# Nova_32kw_FRAM_piggyback.net
KiCad netlist of a schematic drawn in EasyEDA Pro
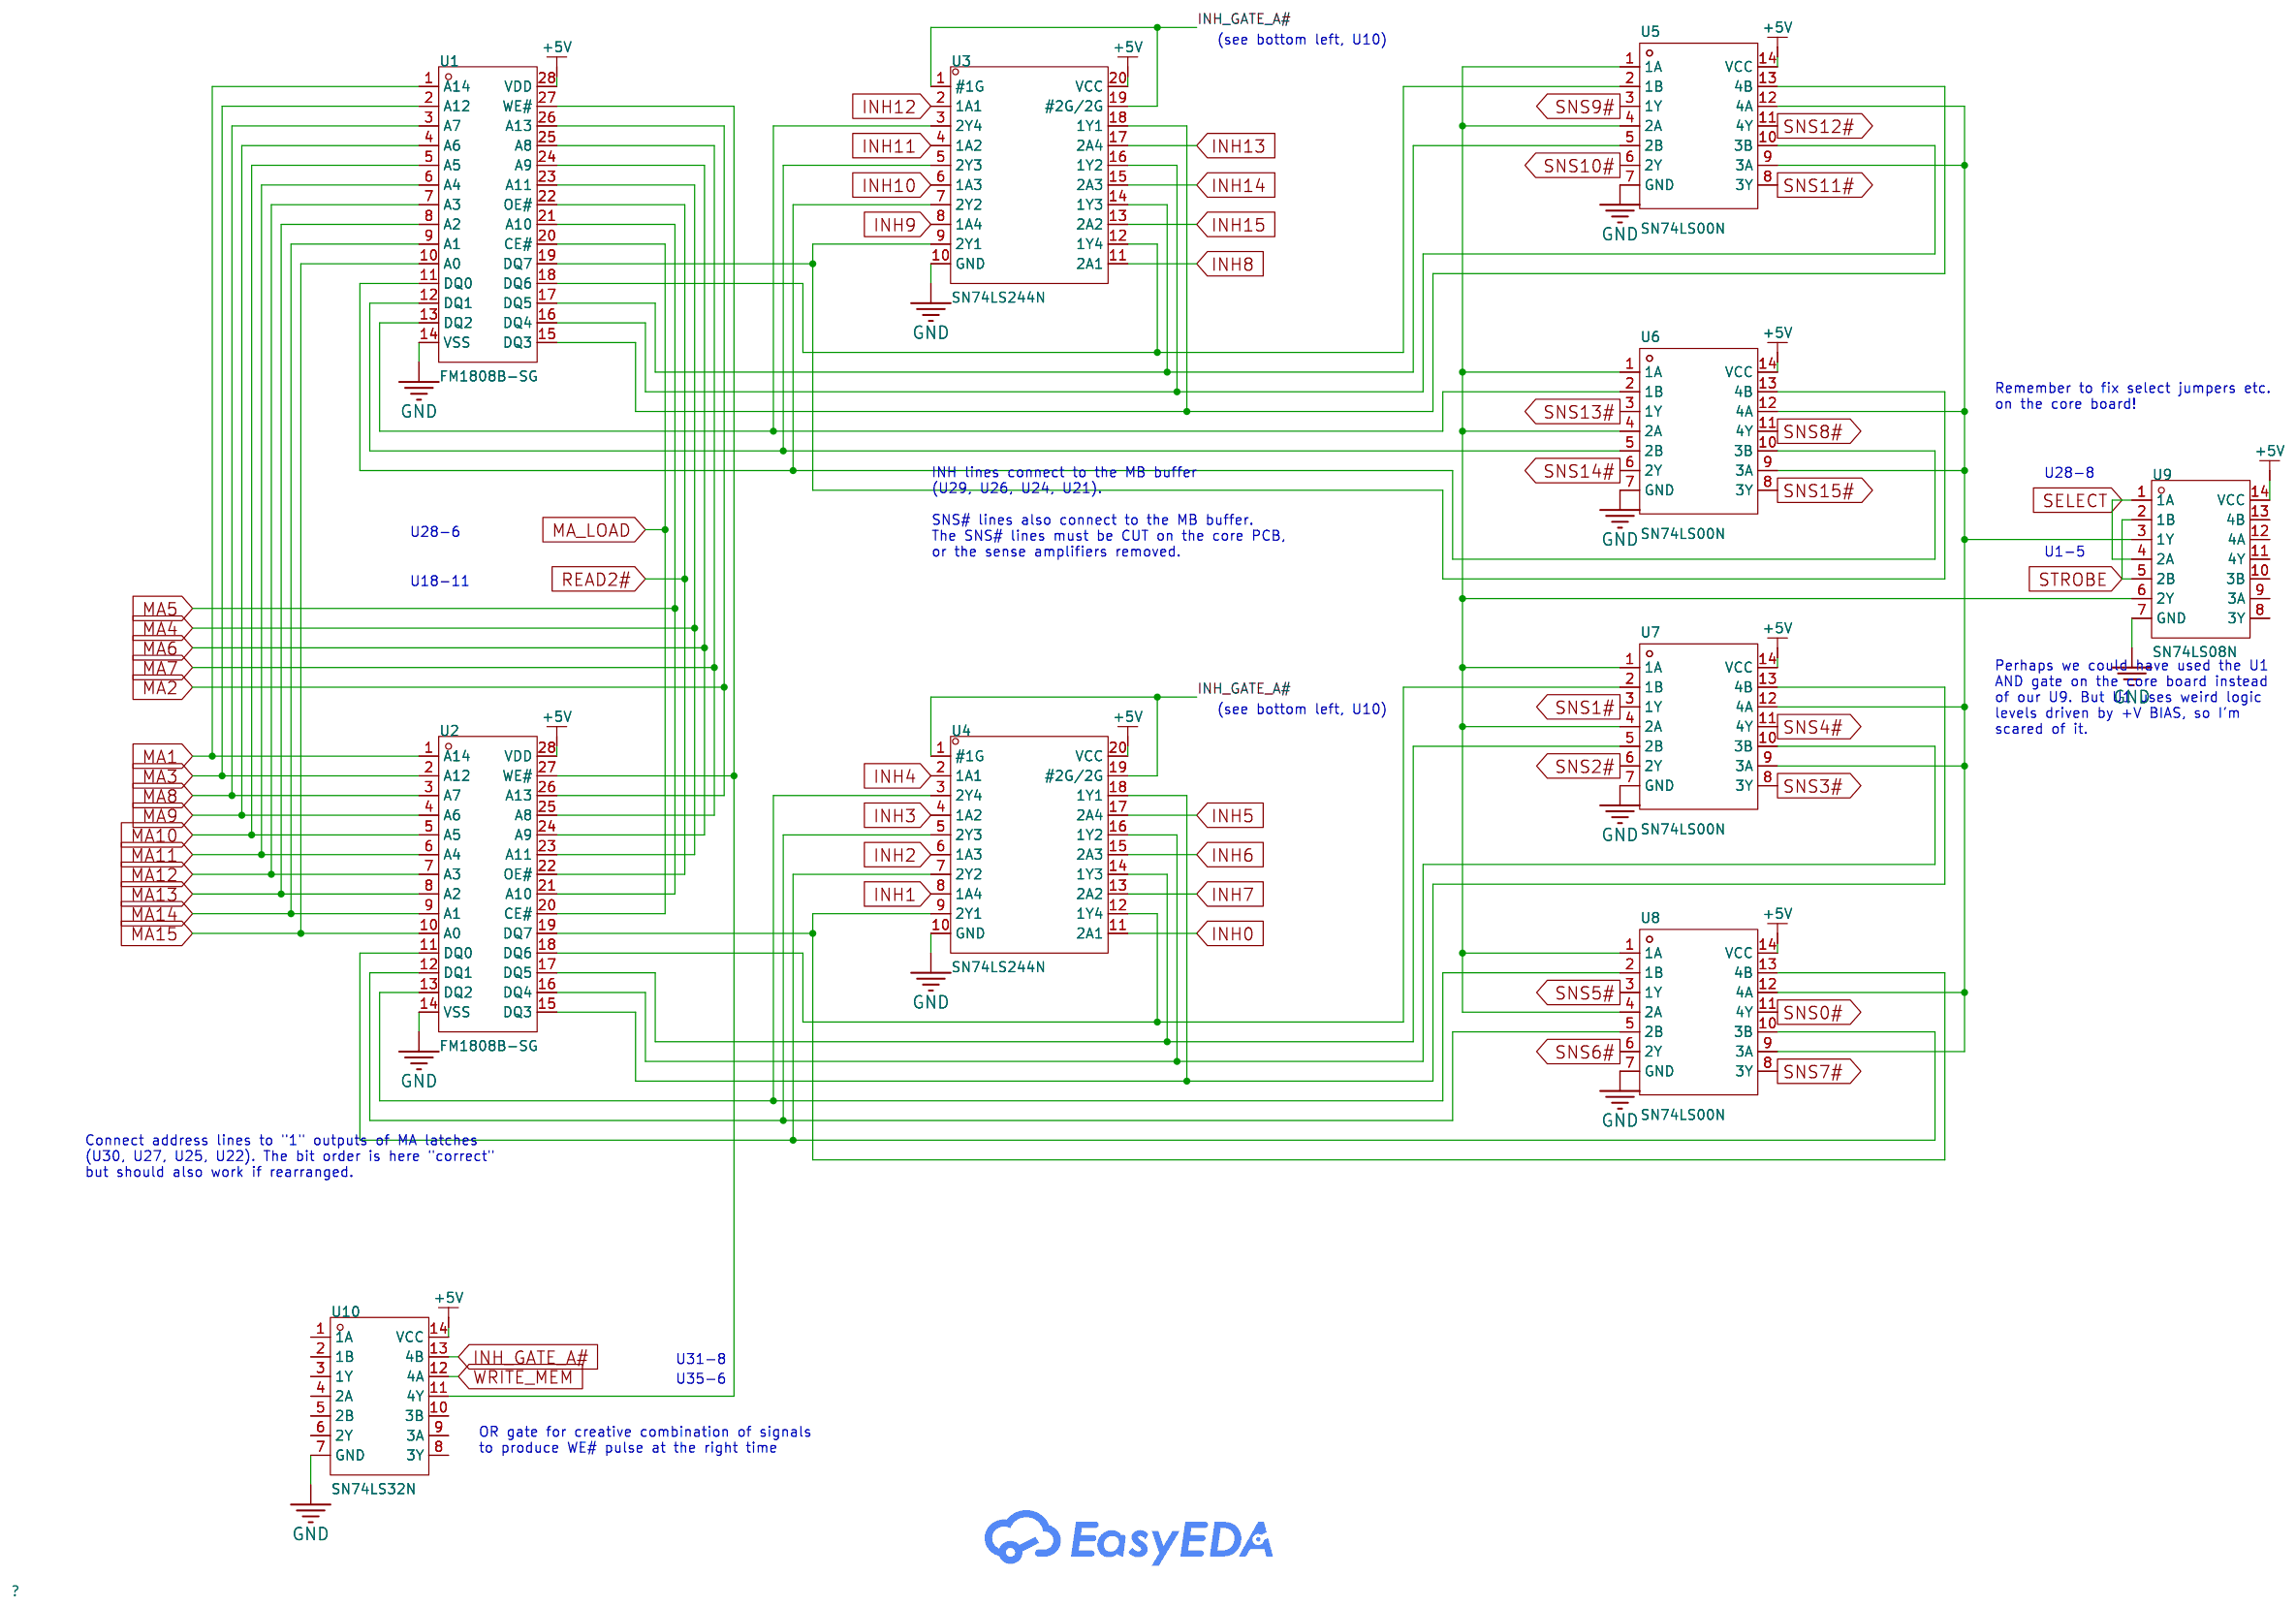
[diagram p0: schematic sheet]

(export (version "E")
  (design (tool "Eeschema 10.0.6"))
  (components
    (comp (ref "U1")
      (value "FM1808B-SG")
      (footprint "easyedapro:SOIC-28_L17.9-W7.5-P1.27-LS10.3-BL")
      (fields (field (name "Manufacturer") "Infineon/CYPRESS(赛普拉斯)"))
      (libsource (lib "easyedapro") (part "FM1808B-SG_C2953762"))
    )
    (comp (ref "U2")
      (value "FM1808B-SG")
      (footprint "easyedapro:SOIC-28_L17.9-W7.5-P1.27-LS10.3-BL")
      (fields (field (name "Manufacturer") "Infineon/CYPRESS(赛普拉斯)"))
      (libsource (lib "easyedapro") (part "FM1808B-SG_C2953762"))
    )
    (comp (ref "U3")
      (value "SN74LS244N")
      (footprint "easyedapro:DIP-20_L25.5-W10.0-P2.54-LS7.6-BL")
      (fields (field (name "Manufacturer") "TI(德州仪器)"))
      (libsource (lib "easyedapro") (part "SN74LS244N"))
    )
    (comp (ref "U4")
      (value "SN74LS244N")
      (footprint "easyedapro:DIP-20_L25.5-W10.0-P2.54-LS7.6-BL")
      (fields (field (name "Manufacturer") "TI(德州仪器)"))
      (libsource (lib "easyedapro") (part "SN74LS244N"))
    )
    (comp (ref "U5")
      (value "SN74LS00N")
      (footprint "easyedapro:PDIP-14_L19.7-W6.6-P2.54-LS8.3-BL")
      (fields (field (name "Manufacturer") "TI(德州仪器)"))
      (libsource (lib "easyedapro") (part "SN74LS00N"))
    )
    (comp (ref "U6")
      (value "SN74LS00N")
      (footprint "easyedapro:PDIP-14_L19.7-W6.6-P2.54-LS8.3-BL")
      (fields (field (name "Manufacturer") "TI(德州仪器)"))
      (libsource (lib "easyedapro") (part "SN74LS00N"))
    )
    (comp (ref "U7")
      (value "SN74LS00N")
      (footprint "easyedapro:PDIP-14_L19.7-W6.6-P2.54-LS8.3-BL")
      (fields (field (name "Manufacturer") "TI(德州仪器)"))
      (libsource (lib "easyedapro") (part "SN74LS00N"))
    )
    (comp (ref "U8")
      (value "SN74LS00N")
      (footprint "easyedapro:PDIP-14_L19.7-W6.6-P2.54-LS8.3-BL")
      (fields (field (name "Manufacturer") "TI(德州仪器)"))
      (libsource (lib "easyedapro") (part "SN74LS00N"))
    )
    (comp (ref "U9")
      (value "SN74LS08N")
      (footprint "easyedapro:PDIP-14_L19.3-W6.4-P2.54-LS7.9-BL-1")
      (fields (field (name "Manufacturer") "TI(德州仪器)"))
      (libsource (lib "easyedapro") (part "SN74LS08N"))
    )
    (comp (ref "U10")
      (value "SN74LS32N")
      (footprint "easyedapro:PDIP-14_L19.6-W6.5-P2.54-LS7.9-BL")
      (fields (field (name "Manufacturer") "TI(德州仪器)"))
      (libsource (lib "easyedapro") (part "SN74LS32N"))
    )
  )
  (nets
    (net (code "1") (name "+5V") (class "Default")
      (node (ref "U1") (pin "28") (pinfunction "VDD_28") (pintype "unspecified"))
      (node (ref "U10") (pin "14") (pinfunction "VCC_14") (pintype "input"))
      (node (ref "U2") (pin "28") (pinfunction "VDD_28") (pintype "unspecified"))
      (node (ref "U3") (pin "20") (pinfunction "VCC_20") (pintype "input"))
      (node (ref "U4") (pin "20") (pinfunction "VCC_20") (pintype "input"))
      (node (ref "U5") (pin "14") (pinfunction "VCC_14") (pintype "unspecified"))
      (node (ref "U6") (pin "14") (pinfunction "VCC_14") (pintype "unspecified"))
      (node (ref "U7") (pin "14") (pinfunction "VCC_14") (pintype "unspecified"))
      (node (ref "U8") (pin "14") (pinfunction "VCC_14") (pintype "unspecified"))
      (node (ref "U9") (pin "14") (pinfunction "VCC_14") (pintype "unspecified"))
    )
    (net (code "2") (name "GND") (class "Default")
      (node (ref "U1") (pin "14") (pinfunction "VSS_14") (pintype "unspecified"))
      (node (ref "U10") (pin "7") (pinfunction "GND_7") (pintype "input"))
      (node (ref "U2") (pin "14") (pinfunction "VSS_14") (pintype "unspecified"))
      (node (ref "U3") (pin "10") (pinfunction "GND_10") (pintype "input"))
      (node (ref "U4") (pin "10") (pinfunction "GND_10") (pintype "input"))
      (node (ref "U5") (pin "7") (pinfunction "GND_7") (pintype "unspecified"))
      (node (ref "U6") (pin "7") (pinfunction "GND_7") (pintype "unspecified"))
      (node (ref "U7") (pin "7") (pinfunction "GND_7") (pintype "unspecified"))
      (node (ref "U8") (pin "7") (pinfunction "GND_7") (pintype "unspecified"))
      (node (ref "U9") (pin "7") (pinfunction "GND_7") (pintype "unspecified"))
    )
    (net (code "3") (name "INH0") (class "Default")
      (node (ref "U4") (pin "11") (pinfunction "2A1_11") (pintype "input"))
    )
    (net (code "4") (name "INH1") (class "Default")
      (node (ref "U4") (pin "8") (pinfunction "1A4_8") (pintype "input"))
    )
    (net (code "5") (name "INH2") (class "Default")
      (node (ref "U4") (pin "6") (pinfunction "1A3_6") (pintype "input"))
    )
    (net (code "6") (name "INH3") (class "Default")
      (node (ref "U4") (pin "4") (pinfunction "1A2_4") (pintype "input"))
    )
    (net (code "7") (name "INH4") (class "Default")
      (node (ref "U4") (pin "2") (pinfunction "1A1_2") (pintype "input"))
    )
    (net (code "8") (name "INH5") (class "Default")
      (node (ref "U4") (pin "17") (pinfunction "2A4_17") (pintype "input"))
    )
    (net (code "9") (name "INH6") (class "Default")
      (node (ref "U4") (pin "15") (pinfunction "2A3_15") (pintype "input"))
    )
    (net (code "10") (name "INH7") (class "Default")
      (node (ref "U4") (pin "13") (pinfunction "2A2_13") (pintype "input"))
    )
    (net (code "11") (name "INH8") (class "Default")
      (node (ref "U3") (pin "11") (pinfunction "2A1_11") (pintype "input"))
    )
    (net (code "12") (name "INH9") (class "Default")
      (node (ref "U3") (pin "8") (pinfunction "1A4_8") (pintype "input"))
    )
    (net (code "13") (name "INH10") (class "Default")
      (node (ref "U3") (pin "6") (pinfunction "1A3_6") (pintype "input"))
    )
    (net (code "14") (name "INH11") (class "Default")
      (node (ref "U3") (pin "4") (pinfunction "1A2_4") (pintype "input"))
    )
    (net (code "15") (name "INH12") (class "Default")
      (node (ref "U3") (pin "2") (pinfunction "1A1_2") (pintype "input"))
    )
    (net (code "16") (name "INH13") (class "Default")
      (node (ref "U3") (pin "17") (pinfunction "2A4_17") (pintype "input"))
    )
    (net (code "17") (name "INH14") (class "Default")
      (node (ref "U3") (pin "15") (pinfunction "2A3_15") (pintype "input"))
    )
    (net (code "18") (name "INH15") (class "Default")
      (node (ref "U3") (pin "13") (pinfunction "2A2_13") (pintype "input"))
    )
    (net (code "19") (name "INH_GATE_A#") (class "Default")
      (node (ref "U10") (pin "13") (pinfunction "4B_13") (pintype "input"))
      (node (ref "U3") (pin "1") (pinfunction "#1G_1") (pintype "input"))
      (node (ref "U3") (pin "19") (pinfunction "#2G/2G_19") (pintype "input"))
      (node (ref "U4") (pin "1") (pinfunction "#1G_1") (pintype "input"))
      (node (ref "U4") (pin "19") (pinfunction "#2G/2G_19") (pintype "input"))
    )
    (net (code "20") (name "MA1") (class "Default")
      (node (ref "U1") (pin "1") (pinfunction "A14_1") (pintype "unspecified"))
      (node (ref "U2") (pin "1") (pinfunction "A14_1") (pintype "unspecified"))
    )
    (net (code "21") (name "MA2") (class "Default")
      (node (ref "U1") (pin "26") (pinfunction "A13_26") (pintype "unspecified"))
      (node (ref "U2") (pin "26") (pinfunction "A13_26") (pintype "unspecified"))
    )
    (net (code "22") (name "MA3") (class "Default")
      (node (ref "U1") (pin "2") (pinfunction "A12_2") (pintype "unspecified"))
      (node (ref "U2") (pin "2") (pinfunction "A12_2") (pintype "unspecified"))
    )
    (net (code "23") (name "MA4") (class "Default")
      (node (ref "U1") (pin "23") (pinfunction "A11_23") (pintype "unspecified"))
      (node (ref "U2") (pin "23") (pinfunction "A11_23") (pintype "unspecified"))
    )
    (net (code "24") (name "MA5") (class "Default")
      (node (ref "U1") (pin "21") (pinfunction "A10_21") (pintype "unspecified"))
      (node (ref "U2") (pin "21") (pinfunction "A10_21") (pintype "unspecified"))
    )
    (net (code "25") (name "MA6") (class "Default")
      (node (ref "U1") (pin "24") (pinfunction "A9_24") (pintype "unspecified"))
      (node (ref "U2") (pin "24") (pinfunction "A9_24") (pintype "unspecified"))
    )
    (net (code "26") (name "MA7") (class "Default")
      (node (ref "U1") (pin "25") (pinfunction "A8_25") (pintype "unspecified"))
      (node (ref "U2") (pin "25") (pinfunction "A8_25") (pintype "unspecified"))
    )
    (net (code "27") (name "MA8") (class "Default")
      (node (ref "U1") (pin "3") (pinfunction "A7_3") (pintype "unspecified"))
      (node (ref "U2") (pin "3") (pinfunction "A7_3") (pintype "unspecified"))
    )
    (net (code "28") (name "MA9") (class "Default")
      (node (ref "U1") (pin "4") (pinfunction "A6_4") (pintype "unspecified"))
      (node (ref "U2") (pin "4") (pinfunction "A6_4") (pintype "unspecified"))
    )
    (net (code "29") (name "MA10") (class "Default")
      (node (ref "U1") (pin "5") (pinfunction "A5_5") (pintype "unspecified"))
      (node (ref "U2") (pin "5") (pinfunction "A5_5") (pintype "unspecified"))
    )
    (net (code "30") (name "MA11") (class "Default")
      (node (ref "U1") (pin "6") (pinfunction "A4_6") (pintype "unspecified"))
      (node (ref "U2") (pin "6") (pinfunction "A4_6") (pintype "unspecified"))
    )
    (net (code "31") (name "MA12") (class "Default")
      (node (ref "U1") (pin "7") (pinfunction "A3_7") (pintype "unspecified"))
      (node (ref "U2") (pin "7") (pinfunction "A3_7") (pintype "unspecified"))
    )
    (net (code "32") (name "MA13") (class "Default")
      (node (ref "U1") (pin "8") (pinfunction "A2_8") (pintype "unspecified"))
      (node (ref "U2") (pin "8") (pinfunction "A2_8") (pintype "unspecified"))
    )
    (net (code "33") (name "MA14") (class "Default")
      (node (ref "U1") (pin "9") (pinfunction "A1_9") (pintype "unspecified"))
      (node (ref "U2") (pin "9") (pinfunction "A1_9") (pintype "unspecified"))
    )
    (net (code "34") (name "MA15") (class "Default")
      (node (ref "U1") (pin "10") (pinfunction "A0_10") (pintype "unspecified"))
      (node (ref "U2") (pin "10") (pinfunction "A0_10") (pintype "unspecified"))
    )
    (net (code "35") (name "MA_LOAD") (class "Default")
      (node (ref "U1") (pin "20") (pinfunction "CE#_20") (pintype "unspecified"))
      (node (ref "U2") (pin "20") (pinfunction "CE#_20") (pintype "unspecified"))
    )
    (net (code "36") (name "Net-(U1-DQ0)") (class "Default")
      (node (ref "U1") (pin "11") (pinfunction "DQ0_11") (pintype "unspecified"))
      (node (ref "U3") (pin "7") (pinfunction "2Y2_7") (pintype "input"))
      (node (ref "U6") (pin "10") (pinfunction "3B_10") (pintype "unspecified"))
    )
    (net (code "37") (name "Net-(U1-DQ1)") (class "Default")
      (node (ref "U1") (pin "12") (pinfunction "DQ1_12") (pintype "unspecified"))
      (node (ref "U3") (pin "5") (pinfunction "2Y3_5") (pintype "input"))
      (node (ref "U6") (pin "5") (pinfunction "2B_5") (pintype "unspecified"))
    )
    (net (code "38") (name "Net-(U1-DQ2)") (class "Default")
      (node (ref "U1") (pin "13") (pinfunction "DQ2_13") (pintype "unspecified"))
      (node (ref "U3") (pin "3") (pinfunction "2Y4_3") (pintype "input"))
      (node (ref "U6") (pin "2") (pinfunction "1B_2") (pintype "unspecified"))
    )
    (net (code "39") (name "Net-(U1-DQ3)") (class "Default")
      (node (ref "U1") (pin "15") (pinfunction "DQ3_15") (pintype "unspecified"))
      (node (ref "U3") (pin "18") (pinfunction "1Y1_18") (pintype "input"))
      (node (ref "U5") (pin "13") (pinfunction "4B_13") (pintype "unspecified"))
    )
    (net (code "40") (name "Net-(U1-DQ4)") (class "Default")
      (node (ref "U1") (pin "16") (pinfunction "DQ4_16") (pintype "unspecified"))
      (node (ref "U3") (pin "16") (pinfunction "1Y2_16") (pintype "input"))
      (node (ref "U5") (pin "10") (pinfunction "3B_10") (pintype "unspecified"))
    )
    (net (code "41") (name "Net-(U1-DQ5)") (class "Default")
      (node (ref "U1") (pin "17") (pinfunction "DQ5_17") (pintype "unspecified"))
      (node (ref "U3") (pin "14") (pinfunction "1Y3_14") (pintype "input"))
      (node (ref "U5") (pin "5") (pinfunction "2B_5") (pintype "unspecified"))
    )
    (net (code "42") (name "Net-(U1-DQ6)") (class "Default")
      (node (ref "U1") (pin "18") (pinfunction "DQ6_18") (pintype "unspecified"))
      (node (ref "U3") (pin "12") (pinfunction "1Y4_12") (pintype "input"))
      (node (ref "U5") (pin "2") (pinfunction "1B_2") (pintype "unspecified"))
    )
    (net (code "43") (name "Net-(U1-DQ7)") (class "Default")
      (node (ref "U1") (pin "19") (pinfunction "DQ7_19") (pintype "unspecified"))
      (node (ref "U3") (pin "9") (pinfunction "2Y1_9") (pintype "input"))
      (node (ref "U6") (pin "13") (pinfunction "4B_13") (pintype "unspecified"))
    )
    (net (code "44") (name "Net-(U1-WE#)") (class "Default")
      (node (ref "U1") (pin "27") (pinfunction "WE#_27") (pintype "unspecified"))
      (node (ref "U10") (pin "11") (pinfunction "4Y_11") (pintype "input"))
      (node (ref "U2") (pin "27") (pinfunction "WE#_27") (pintype "unspecified"))
    )
    (net (code "45") (name "Net-(U2-DQ0)") (class "Default")
      (node (ref "U2") (pin "11") (pinfunction "DQ0_11") (pintype "unspecified"))
      (node (ref "U4") (pin "7") (pinfunction "2Y2_7") (pintype "input"))
      (node (ref "U8") (pin "10") (pinfunction "3B_10") (pintype "unspecified"))
    )
    (net (code "46") (name "Net-(U2-DQ1)") (class "Default")
      (node (ref "U2") (pin "12") (pinfunction "DQ1_12") (pintype "unspecified"))
      (node (ref "U4") (pin "5") (pinfunction "2Y3_5") (pintype "input"))
      (node (ref "U8") (pin "5") (pinfunction "2B_5") (pintype "unspecified"))
    )
    (net (code "47") (name "Net-(U2-DQ2)") (class "Default")
      (node (ref "U2") (pin "13") (pinfunction "DQ2_13") (pintype "unspecified"))
      (node (ref "U4") (pin "3") (pinfunction "2Y4_3") (pintype "input"))
      (node (ref "U8") (pin "2") (pinfunction "1B_2") (pintype "unspecified"))
    )
    (net (code "48") (name "Net-(U2-DQ3)") (class "Default")
      (node (ref "U2") (pin "15") (pinfunction "DQ3_15") (pintype "unspecified"))
      (node (ref "U4") (pin "18") (pinfunction "1Y1_18") (pintype "input"))
      (node (ref "U7") (pin "13") (pinfunction "4B_13") (pintype "unspecified"))
    )
    (net (code "49") (name "Net-(U2-DQ4)") (class "Default")
      (node (ref "U2") (pin "16") (pinfunction "DQ4_16") (pintype "unspecified"))
      (node (ref "U4") (pin "16") (pinfunction "1Y2_16") (pintype "input"))
      (node (ref "U7") (pin "10") (pinfunction "3B_10") (pintype "unspecified"))
    )
    (net (code "50") (name "Net-(U2-DQ5)") (class "Default")
      (node (ref "U2") (pin "17") (pinfunction "DQ5_17") (pintype "unspecified"))
      (node (ref "U4") (pin "14") (pinfunction "1Y3_14") (pintype "input"))
      (node (ref "U7") (pin "5") (pinfunction "2B_5") (pintype "unspecified"))
    )
    (net (code "51") (name "Net-(U2-DQ6)") (class "Default")
      (node (ref "U2") (pin "18") (pinfunction "DQ6_18") (pintype "unspecified"))
      (node (ref "U4") (pin "12") (pinfunction "1Y4_12") (pintype "input"))
      (node (ref "U7") (pin "2") (pinfunction "1B_2") (pintype "unspecified"))
    )
    (net (code "52") (name "Net-(U2-DQ7)") (class "Default")
      (node (ref "U2") (pin "19") (pinfunction "DQ7_19") (pintype "unspecified"))
      (node (ref "U4") (pin "9") (pinfunction "2Y1_9") (pintype "input"))
      (node (ref "U8") (pin "13") (pinfunction "4B_13") (pintype "unspecified"))
    )
    (net (code "53") (name "Net-(U5-1A)") (class "Default")
      (node (ref "U5") (pin "1") (pinfunction "1A_1") (pintype "unspecified"))
      (node (ref "U5") (pin "4") (pinfunction "2A_4") (pintype "unspecified"))
      (node (ref "U6") (pin "1") (pinfunction "1A_1") (pintype "unspecified"))
      (node (ref "U6") (pin "4") (pinfunction "2A_4") (pintype "unspecified"))
      (node (ref "U7") (pin "1") (pinfunction "1A_1") (pintype "unspecified"))
      (node (ref "U7") (pin "4") (pinfunction "2A_4") (pintype "unspecified"))
      (node (ref "U8") (pin "1") (pinfunction "1A_1") (pintype "unspecified"))
      (node (ref "U8") (pin "4") (pinfunction "2A_4") (pintype "unspecified"))
      (node (ref "U9") (pin "6") (pinfunction "2Y_6") (pintype "unspecified"))
    )
    (net (code "54") (name "Net-(U5-3A)") (class "Default")
      (node (ref "U5") (pin "12") (pinfunction "4A_12") (pintype "unspecified"))
      (node (ref "U5") (pin "9") (pinfunction "3A_9") (pintype "unspecified"))
      (node (ref "U6") (pin "12") (pinfunction "4A_12") (pintype "unspecified"))
      (node (ref "U6") (pin "9") (pinfunction "3A_9") (pintype "unspecified"))
      (node (ref "U7") (pin "12") (pinfunction "4A_12") (pintype "unspecified"))
      (node (ref "U7") (pin "9") (pinfunction "3A_9") (pintype "unspecified"))
      (node (ref "U8") (pin "12") (pinfunction "4A_12") (pintype "unspecified"))
      (node (ref "U8") (pin "9") (pinfunction "3A_9") (pintype "unspecified"))
      (node (ref "U9") (pin "3") (pinfunction "1Y_3") (pintype "unspecified"))
    )
    (net (code "55") (name "READ2#") (class "Default")
      (node (ref "U1") (pin "22") (pinfunction "OE#_22") (pintype "unspecified"))
      (node (ref "U2") (pin "22") (pinfunction "OE#_22") (pintype "unspecified"))
    )
    (net (code "56") (name "SELECT") (class "Default")
      (node (ref "U9") (pin "1") (pinfunction "1A_1") (pintype "unspecified"))
      (node (ref "U9") (pin "4") (pinfunction "2A_4") (pintype "unspecified"))
    )
    (net (code "57") (name "SNS0#") (class "Default")
      (node (ref "U8") (pin "11") (pinfunction "4Y_11") (pintype "unspecified"))
    )
    (net (code "58") (name "SNS1#") (class "Default")
      (node (ref "U7") (pin "3") (pinfunction "1Y_3") (pintype "unspecified"))
    )
    (net (code "59") (name "SNS2#") (class "Default")
      (node (ref "U7") (pin "6") (pinfunction "2Y_6") (pintype "unspecified"))
    )
    (net (code "60") (name "SNS3#") (class "Default")
      (node (ref "U7") (pin "8") (pinfunction "3Y_8") (pintype "unspecified"))
    )
    (net (code "61") (name "SNS4#") (class "Default")
      (node (ref "U7") (pin "11") (pinfunction "4Y_11") (pintype "unspecified"))
    )
    (net (code "62") (name "SNS5#") (class "Default")
      (node (ref "U8") (pin "3") (pinfunction "1Y_3") (pintype "unspecified"))
    )
    (net (code "63") (name "SNS6#") (class "Default")
      (node (ref "U8") (pin "6") (pinfunction "2Y_6") (pintype "unspecified"))
    )
    (net (code "64") (name "SNS7#") (class "Default")
      (node (ref "U8") (pin "8") (pinfunction "3Y_8") (pintype "unspecified"))
    )
    (net (code "65") (name "SNS8#") (class "Default")
      (node (ref "U6") (pin "11") (pinfunction "4Y_11") (pintype "unspecified"))
    )
    (net (code "66") (name "SNS9#") (class "Default")
      (node (ref "U5") (pin "3") (pinfunction "1Y_3") (pintype "unspecified"))
    )
    (net (code "67") (name "SNS10#") (class "Default")
      (node (ref "U5") (pin "6") (pinfunction "2Y_6") (pintype "unspecified"))
    )
    (net (code "68") (name "SNS11#") (class "Default")
      (node (ref "U5") (pin "8") (pinfunction "3Y_8") (pintype "unspecified"))
    )
    (net (code "69") (name "SNS12#") (class "Default")
      (node (ref "U5") (pin "11") (pinfunction "4Y_11") (pintype "unspecified"))
    )
    (net (code "70") (name "SNS13#") (class "Default")
      (node (ref "U6") (pin "3") (pinfunction "1Y_3") (pintype "unspecified"))
    )
    (net (code "71") (name "SNS14#") (class "Default")
      (node (ref "U6") (pin "6") (pinfunction "2Y_6") (pintype "unspecified"))
    )
    (net (code "72") (name "SNS15#") (class "Default")
      (node (ref "U6") (pin "8") (pinfunction "3Y_8") (pintype "unspecified"))
    )
    (net (code "73") (name "STROBE") (class "Default")
      (node (ref "U9") (pin "2") (pinfunction "1B_2") (pintype "unspecified"))
      (node (ref "U9") (pin "5") (pinfunction "2B_5") (pintype "unspecified"))
    )
    (net (code "74") (name "WRITE_MEM") (class "Default")
      (node (ref "U10") (pin "12") (pinfunction "4A_12") (pintype "input"))
    )
    (net (code "75") (name "unconnected-(U9-3A-Pad9)") (class "Default")
      (node (ref "U9") (pin "9") (pinfunction "3A_9") (pintype "unspecified"))
    )
    (net (code "76") (name "unconnected-(U9-3B-Pad10)") (class "Default")
      (node (ref "U9") (pin "10") (pinfunction "3B_10") (pintype "unspecified"))
    )
    (net (code "77") (name "unconnected-(U9-3Y-Pad8)") (class "Default")
      (node (ref "U9") (pin "8") (pinfunction "3Y_8") (pintype "unspecified"))
    )
    (net (code "78") (name "unconnected-(U9-4A-Pad12)") (class "Default")
      (node (ref "U9") (pin "12") (pinfunction "4A_12") (pintype "unspecified"))
    )
    (net (code "79") (name "unconnected-(U9-4B-Pad13)") (class "Default")
      (node (ref "U9") (pin "13") (pinfunction "4B_13") (pintype "unspecified"))
    )
    (net (code "80") (name "unconnected-(U9-4Y-Pad11)") (class "Default")
      (node (ref "U9") (pin "11") (pinfunction "4Y_11") (pintype "unspecified"))
    )
    (net (code "81") (name "unconnected-(U10-1A-Pad1)") (class "Default")
      (node (ref "U10") (pin "1") (pinfunction "1A_1") (pintype "input"))
    )
    (net (code "82") (name "unconnected-(U10-1B-Pad2)") (class "Default")
      (node (ref "U10") (pin "2") (pinfunction "1B_2") (pintype "input"))
    )
    (net (code "83") (name "unconnected-(U10-1Y-Pad3)") (class "Default")
      (node (ref "U10") (pin "3") (pinfunction "1Y_3") (pintype "input"))
    )
    (net (code "84") (name "unconnected-(U10-2A-Pad4)") (class "Default")
      (node (ref "U10") (pin "4") (pinfunction "2A_4") (pintype "input"))
    )
    (net (code "85") (name "unconnected-(U10-2B-Pad5)") (class "Default")
      (node (ref "U10") (pin "5") (pinfunction "2B_5") (pintype "input"))
    )
    (net (code "86") (name "unconnected-(U10-2Y-Pad6)") (class "Default")
      (node (ref "U10") (pin "6") (pinfunction "2Y_6") (pintype "input"))
    )
    (net (code "87") (name "unconnected-(U10-3A-Pad9)") (class "Default")
      (node (ref "U10") (pin "9") (pinfunction "3A_9") (pintype "input"))
    )
    (net (code "88") (name "unconnected-(U10-3B-Pad10)") (class "Default")
      (node (ref "U10") (pin "10") (pinfunction "3B_10") (pintype "input"))
    )
    (net (code "89") (name "unconnected-(U10-3Y-Pad8)") (class "Default")
      (node (ref "U10") (pin "8") (pinfunction "3Y_8") (pintype "input"))
    )
  )
)
